# Schematics.net
KiCad netlist of a schematic drawn in Altium Designer
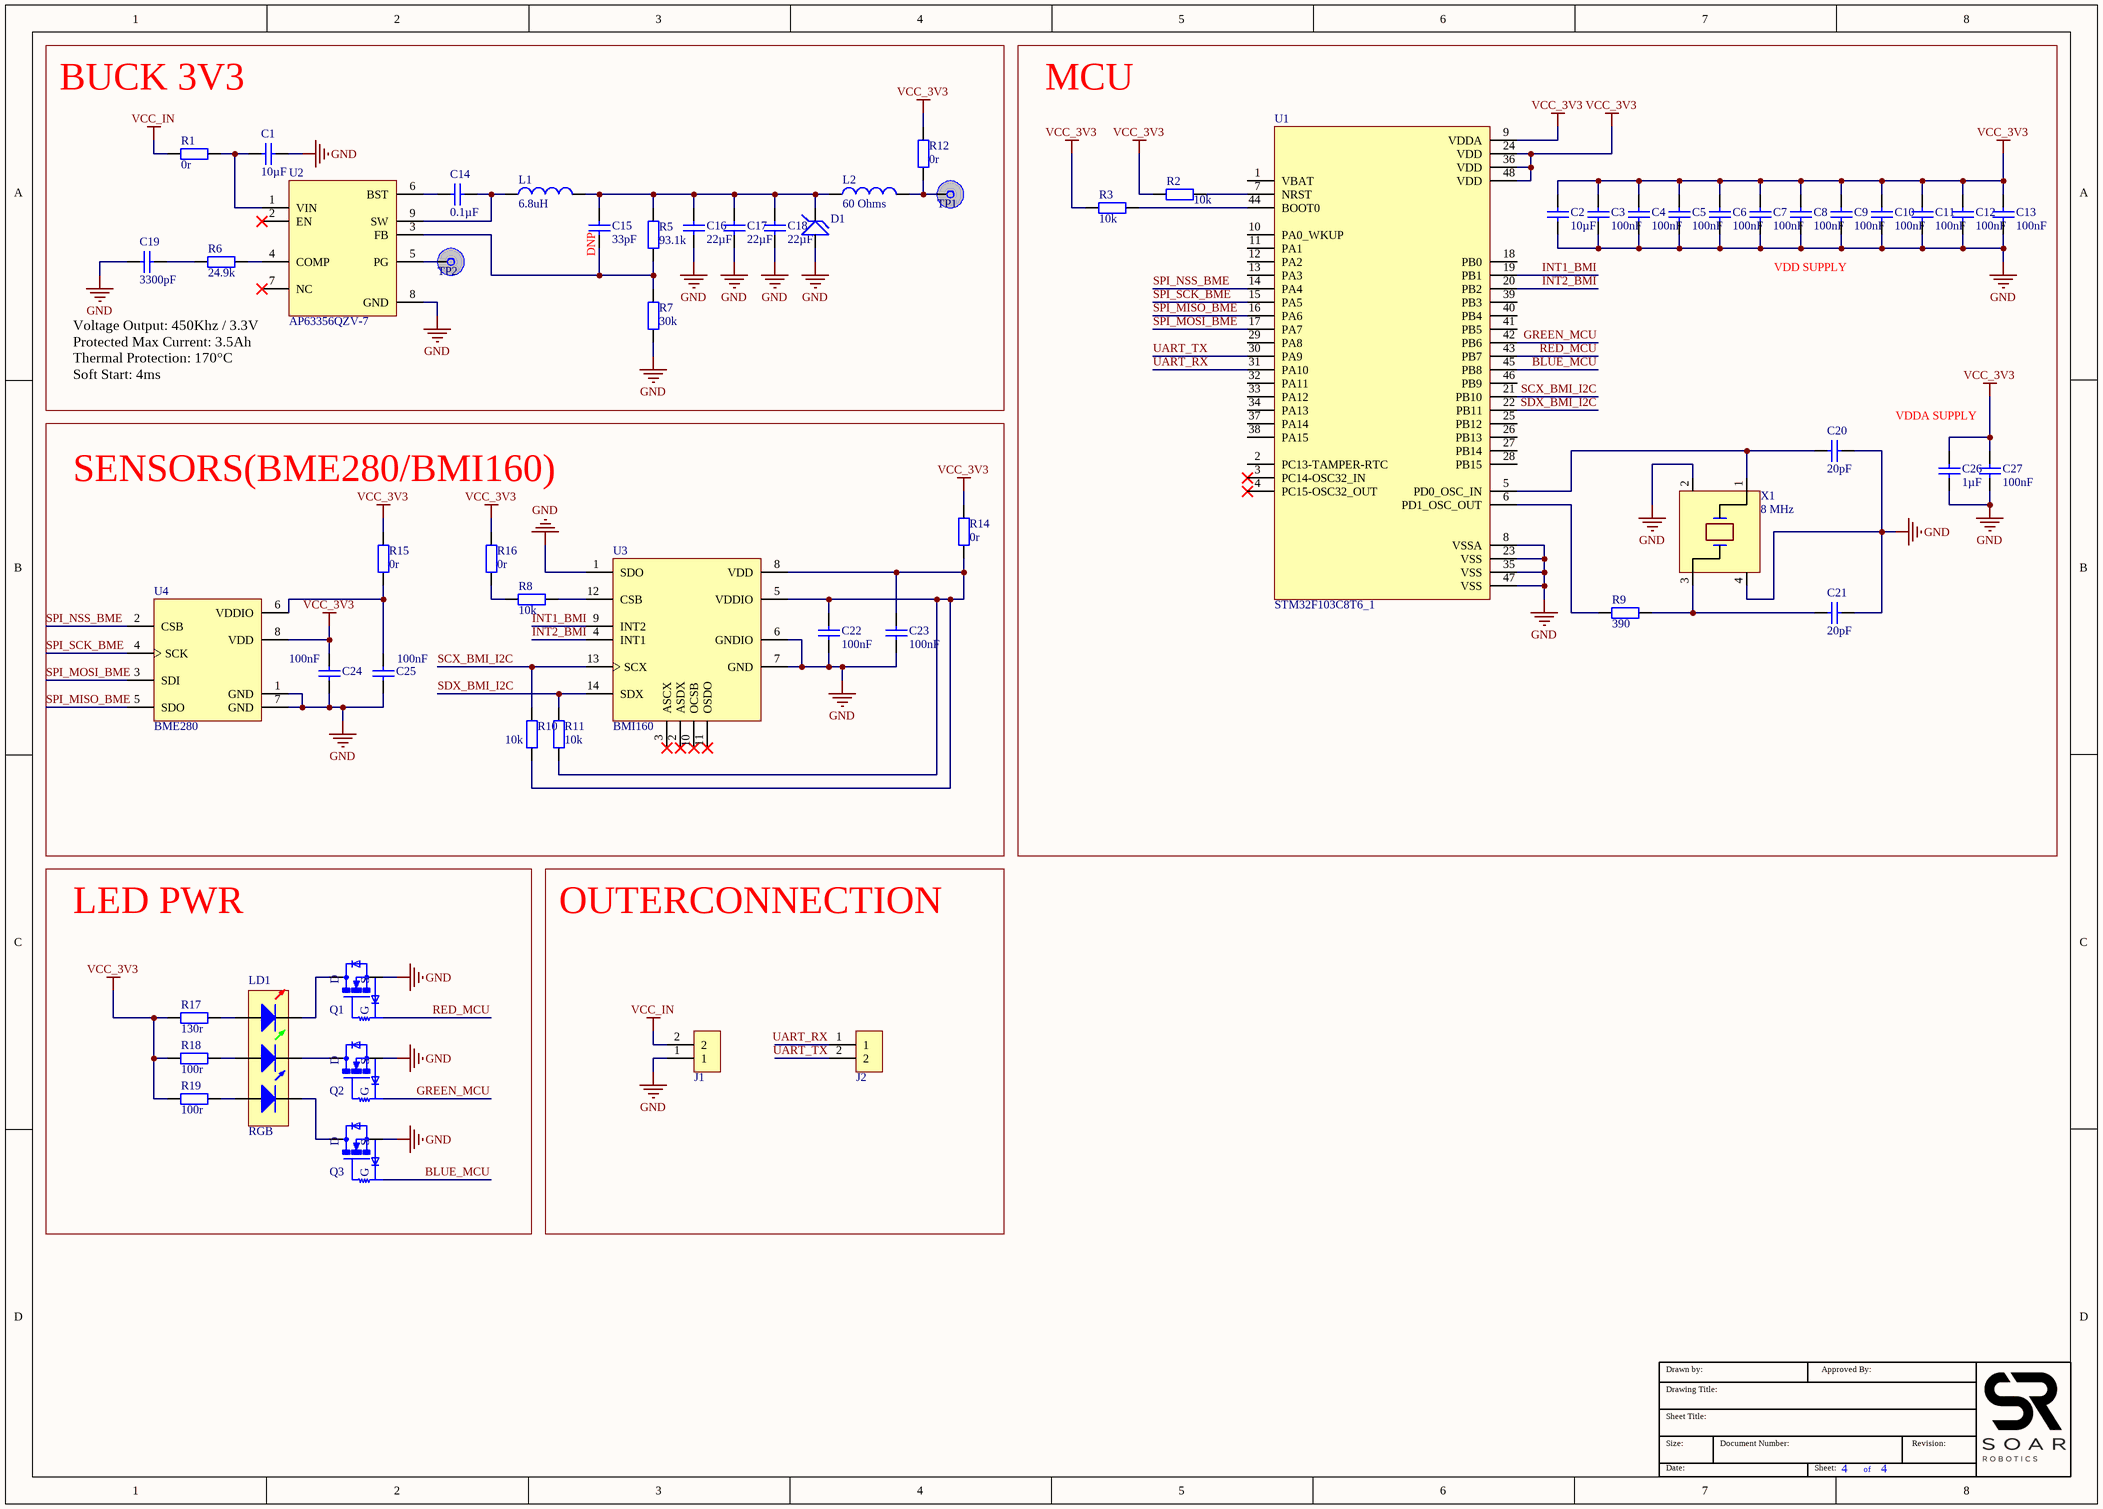
[diagram p0: Schematics.SchDoc]

(export (version "E")
  (design (tool "Eeschema 10.0.6"))
  (components
    (comp (ref "C1")
      (value "10µF")
      (footprint "CAP_0805")
      (description "10 µF ±10% 50V Ceramic Capacitor X5R 0805 (2012 Metric)")
      (fields (field (name "MANUFACTURER PART NUMBER") "GRM21BR61H106KE43L") (field (name "VOLTAGE") "50V"))
      (libsource (lib "MyCapLib") (part "GRM21BR61H106KE43L"))
    )
    (comp (ref "C2")
      (value "10µF")
      (footprint "CAP_0402")
      (description "10µF ±20% 6.3V Ceramic Capacitor X5R 0402 (1005 Metric)")
      (fields (field (name "MANUFACTURER PART NUMBER") "GRJ155R60J106ME11D") (field (name "VOLTAGE") "6.3V"))
      (libsource (lib "MyCapLib") (part "GRJ155R60J106ME11D"))
    )
    (comp (ref "C3")
      (value "100nF")
      (footprint "CAP_0603")
      (fields (field (name "Comment") "CAP"))
      (libsource (lib "MyCapLib") (part "CAP"))
    )
    (comp (ref "C4")
      (value "100nF")
      (footprint "CAP_0603")
      (fields (field (name "Comment") "CAP"))
      (libsource (lib "MyCapLib") (part "CAP"))
    )
    (comp (ref "C5")
      (value "100nF")
      (footprint "CAP_0603")
      (fields (field (name "Comment") "CAP"))
      (libsource (lib "MyCapLib") (part "CAP"))
    )
    (comp (ref "C6")
      (value "100nF")
      (footprint "CAP_0603")
      (fields (field (name "Comment") "CAP"))
      (libsource (lib "MyCapLib") (part "CAP"))
    )
    (comp (ref "C7")
      (value "100nF")
      (footprint "CAP_0603")
      (fields (field (name "Comment") "CAP"))
      (libsource (lib "MyCapLib") (part "CAP"))
    )
    (comp (ref "C8")
      (value "100nF")
      (footprint "CAP_0603")
      (fields (field (name "Comment") "CAP"))
      (libsource (lib "MyCapLib") (part "CAP"))
    )
    (comp (ref "C9")
      (value "100nF")
      (footprint "CAP_0603")
      (fields (field (name "Comment") "CAP"))
      (libsource (lib "MyCapLib") (part "CAP"))
    )
    (comp (ref "C10")
      (value "100nF")
      (footprint "CAP_0603")
      (fields (field (name "Comment") "CAP"))
      (libsource (lib "MyCapLib") (part "CAP"))
    )
    (comp (ref "C11")
      (value "100nF")
      (footprint "CAP_0603")
      (fields (field (name "Comment") "CAP"))
      (libsource (lib "MyCapLib") (part "CAP"))
    )
    (comp (ref "C12")
      (value "100nF")
      (footprint "CAP_0603")
      (fields (field (name "Comment") "CAP"))
      (libsource (lib "MyCapLib") (part "CAP"))
    )
    (comp (ref "C13")
      (value "100nF")
      (footprint "CAP_0603")
      (fields (field (name "Comment") "CAP"))
      (libsource (lib "MyCapLib") (part "CAP"))
    )
    (comp (ref "C14")
      (value "0.1µF")
      (footprint "CAP_0402")
      (description "0.1 µF ±10% 50V Ceramic Capacitor X7R 0402 (1005 Metric)")
      (fields (field (name "MANUFACTURER PART NUMBER") "04025C104KAT2A") (field (name "VOLTAGE") "50V"))
      (libsource (lib "MyCapLib") (part "04025C104KAT2A"))
    )
    (comp (ref "C15")
      (value "33pF")
      (footprint "CAP_0402")
      (description "33pF ±5% 50V Ceramic Capacitor C0G, NP0 0402 (1005 Metric)")
      (fields (field (name "MANUFACTURER PART NUMBER") "CL05C330JB5NNNC") (field (name "VOLTAGE") "50V"))
      (libsource (lib "MyCapLib") (part "CL05C330JB5NNNC"))
    )
    (comp (ref "C16")
      (value "22µF")
      (footprint "CAP_0603")
      (description "22 µF ±20% 6.3V Ceramic Capacitor X5R 0603 (1608 Metric)")
      (fields (field (name "MANUFACTURER PART NUMBER") "GRM188R60J226MEA0D") (field (name "VOLTAGE") "6.3V"))
      (libsource (lib "MyCapLib") (part "GRM188R60J226MEA0D"))
    )
    (comp (ref "C17")
      (value "22µF")
      (footprint "CAP_0603")
      (description "22 µF ±20% 6.3V Ceramic Capacitor X5R 0603 (1608 Metric)")
      (fields (field (name "MANUFACTURER PART NUMBER") "GRM188R60J226MEA0D") (field (name "VOLTAGE") "6.3V"))
      (libsource (lib "MyCapLib") (part "GRM188R60J226MEA0D"))
    )
    (comp (ref "C18")
      (value "22µF")
      (footprint "CAP_0603")
      (description "22 µF ±20% 6.3V Ceramic Capacitor X5R 0603 (1608 Metric)")
      (fields (field (name "MANUFACTURER PART NUMBER") "GRM188R60J226MEA0D") (field (name "VOLTAGE") "6.3V"))
      (libsource (lib "MyCapLib") (part "GRM188R60J226MEA0D"))
    )
    (comp (ref "C19")
      (value "3300pF")
      (footprint "CAP_0402")
      (description "3300pF ±10% 50V Ceramic Capacitor X7R 0402 (1005 Metric)")
      (fields (field (name "MANUFACTURER PART NUMBER") "CL05B332KB5NNNC") (field (name "VOLTAGE") "50V"))
      (libsource (lib "MyCapLib") (part "CL05B332KB5NNNC"))
    )
    (comp (ref "C20")
      (value "20pF")
      (footprint "CAP_0402")
      (description "20pF ±2% 50V Ceramic Capacitor C0G, NP0 0402 (1005 Metric)")
      (fields (field (name "MANUFACTURER PART NUMBER") "CC0402GRNPO9BN200") (field (name "VOLTAGE") "50v"))
      (libsource (lib "MyCapLib") (part "CC0402GRNPO9BN200"))
    )
    (comp (ref "C21")
      (value "20pF")
      (footprint "CAP_0402")
      (description "20pF ±2% 50V Ceramic Capacitor C0G, NP0 0402 (1005 Metric)")
      (fields (field (name "MANUFACTURER PART NUMBER") "CC0402GRNPO9BN200") (field (name "VOLTAGE") "50v"))
      (libsource (lib "MyCapLib") (part "CC0402GRNPO9BN200"))
    )
    (comp (ref "C22")
      (value "100nF")
      (footprint "CAP_0603")
      (fields (field (name "Comment") "CAP"))
      (libsource (lib "MyCapLib") (part "CAP"))
    )
    (comp (ref "C23")
      (value "100nF")
      (footprint "CAP_0603")
      (fields (field (name "Comment") "CAP"))
      (libsource (lib "MyCapLib") (part "CAP"))
    )
    (comp (ref "C24")
      (value "100nF")
      (footprint "CAP_0603")
      (fields (field (name "Comment") "CAP"))
      (libsource (lib "MyCapLib") (part "CAP"))
    )
    (comp (ref "C25")
      (value "100nF")
      (footprint "CAP_0603")
      (fields (field (name "Comment") "CAP"))
      (libsource (lib "MyCapLib") (part "CAP"))
    )
    (comp (ref "C26")
      (value "1µF")
      (footprint "CAP_0805")
      (description "1µF ±10% 25V Ceramic Capacitor X7R 0805 (2012 Metric)")
      (fields (field (name "MANUFACTURER PART NUMBER") "CL21B105KAFNFNE") (field (name "VOLTAGE") "25V"))
      (libsource (lib "MyCapLib") (part "CL21B105KAFNFNE"))
    )
    (comp (ref "C27")
      (value "100nF")
      (footprint "CAP_0603")
      (fields (field (name "Comment") "CAP"))
      (libsource (lib "MyCapLib") (part "CAP"))
    )
    (comp (ref "D1")
      (value "D6V3H1U2LP16-7")
      (footprint "U-DFN1610-2")
      (description "TVS DIODE 6.3V 11.5V U-DFN1610-2")
      (libsource (lib "MyDiodeLib") (part "D6V3H1U2LP16-7"))
    )
    (comp (ref "J1")
      (value "PRPC001DAAN-RC")
      (footprint "Header x2 Through Hole")
      (description "Connector Header Through Hole 2 position  2.54mm")
      (libsource (lib "MyConLib") (part "PRPC001DAAN-RC"))
    )
    (comp (ref "J2")
      (value "M50-3630242")
      (footprint "1.27MM 2X1 HEADER")
      (description "Connector Header Surface Mount 2 position 0.050\" (1.27mm)")
      (libsource (lib "MyConLib") (part "M50-3630242"))
    )
    (comp (ref "L1")
      (value "6.8uH")
      (footprint "74439346068")
      (description "6.8 µH Shielded Drum Core, Wirewound Inductor 6.5 A 17.6mOhm Nonstandard")
      (fields (field (name "MANUFACTURER PART NUMBER") "74439346068"))
      (libsource (lib "MyIndLib") (part "74439346068"))
    )
    (comp (ref "L2")
      (value "60 Ohms")
      (footprint "IND_0805")
      (description "60 Ohms @ 100MHz 1 Power Line Ferrite Bead 0805 (2012 Metric) 3.5A 20mOhm")
      (fields (field (name "MANUFACTURER PART NUMBER") "BLM21PG600SH1D"))
      (libsource (lib "MyIndLib") (part "BLM21PG600SH1D"))
    )
    (comp (ref "LD1")
      (value "EAST1616RGBB8")
      (footprint "SMD-RGB(1.60x1.60)")
      (fields (field (name "VOLTAGE") "2.05V Red, 2.2V Green, 2.2V Blue") (field (name "COLOR") "RGB"))
      (libsource (lib "MyLedLib") (part "EAST1616RGBB8"))
    )
    (comp (ref "Q1")
      (value "CSD13381F4")
      (footprint "3-XFDFN")
      (description "N-Channel 12 V 2.1A (Ta) 500mW (Ta) Surface Mount 3-PICOSTAR")
      (libsource (lib "MyMosfetLib") (part "CSD13381F4"))
    )
    (comp (ref "Q2")
      (value "CSD13381F4")
      (footprint "3-XFDFN")
      (description "N-Channel 12 V 2.1A (Ta) 500mW (Ta) Surface Mount 3-PICOSTAR")
      (libsource (lib "MyMosfetLib") (part "CSD13381F4"))
    )
    (comp (ref "Q3")
      (value "CSD13381F4")
      (footprint "3-XFDFN")
      (description "N-Channel 12 V 2.1A (Ta) 500mW (Ta) Surface Mount 3-PICOSTAR")
      (libsource (lib "MyMosfetLib") (part "CSD13381F4"))
    )
    (comp (ref "R1")
      (value "0r")
      (footprint "RES_0402")
      (description "RES SMD 0 OHM JUMPER 1/16W 0402")
      (fields (field (name "MANUFACTURER PART NUMBER") "RC0402JR-070RL") (field (name "POWER") "1/16w"))
      (libsource (lib "") (part "RC0402JR-070RL_1"))
    )
    (comp (ref "R2")
      (value "10k")
      (footprint "RES_0402")
      (description "RES 10K OHM 1% 1/16W 0402")
      (fields (field (name "TOLERANCE") "%1") (field (name "POWER") "1/16w"))
      (libsource (lib "") (part "RMCF0402FT10K0_2"))
    )
    (comp (ref "R3")
      (value "10k")
      (footprint "RES_0402")
      (description "RES 10K OHM 1% 1/16W 0402")
      (fields (field (name "TOLERANCE") "%1") (field (name "POWER") "1/16w"))
      (libsource (lib "MyResLib") (part "RMCF0402FT10K0"))
    )
    (comp (ref "R5")
      (value "93.1k")
      (footprint "RES_0402")
      (description "93.1 kOhms ±1% 0.063W, 1/16W Chip Resistor 0402 (1005 Metric) Moisture Resistant Thick Film")
      (fields (field (name "MANUFACTURER PART NUMBER") "RC0402FR-0793K1L") (field (name "POWER") "1/16w"))
      (libsource (lib "MyResLib") (part "RC0402FR-0793K1L"))
    )
    (comp (ref "R6")
      (value "24.9k")
      (footprint "RES_0402")
      (description "RES 24.9K OHM 1% 1/16W 0402")
      (fields (field (name "MANUFACTURER PART NUMBER") "RMCF0402FT24K9") (field (name "POWER") "1/16W"))
      (libsource (lib "MyResLib") (part "RMCF0402FT24K9"))
    )
    (comp (ref "R7")
      (value "30k")
      (footprint "RES_0402")
      (description "RES SMD 30K OHM 1% 1/16W 0402")
      (fields (field (name "MANUFACTURER PART NUMBER") "RC0402FR-0730KL") (field (name "POWER") "1/16w"))
      (libsource (lib "MyResLib") (part "RC0402FR-0730KL"))
    )
    (comp (ref "R8")
      (value "10k")
      (footprint "RES_0402")
      (description "RES 10K OHM 1% 1/16W 0402")
      (fields (field (name "TOLERANCE") "%1") (field (name "POWER") "1/16w"))
      (libsource (lib "MyResLib") (part "RMCF0402FT10K0"))
    )
    (comp (ref "R9")
      (value "390")
      (footprint "RES_0402")
      (description "390 Ohms ±1% 0.063W, 1/16W Chip Resistor 0402 (1005 Metric) Moisture Resistant Thick Film")
      (fields (field (name "MANUFACTURER PART NUMBER") "RC0402FR-07390RL") (field (name "POWER") "1/16W"))
      (libsource (lib "MyResLib") (part "RC0402FR-07390RL"))
    )
    (comp (ref "R10")
      (value "10k")
      (footprint "RES_0402")
      (description "RES 10K OHM 1% 1/16W 0402")
      (fields (field (name "TOLERANCE") "%1") (field (name "POWER") "1/16w"))
      (libsource (lib "") (part "RMCF0402FT10K0_1"))
    )
    (comp (ref "R11")
      (value "10k")
      (footprint "RES_0402")
      (description "RES 10K OHM 1% 1/16W 0402")
      (fields (field (name "TOLERANCE") "%1") (field (name "POWER") "1/16w"))
      (libsource (lib "") (part "RMCF0402FT10K0_1"))
    )
    (comp (ref "R12")
      (value "0r")
      (footprint "RES_0402")
      (description "RES SMD 0 OHM JUMPER 1/16W 0402")
      (fields (field (name "MANUFACTURER PART NUMBER") "RC0402JR-070RL") (field (name "POWER") "1/16w"))
      (libsource (lib "MyResLib") (part "RC0402JR-070RL"))
    )
    (comp (ref "R14")
      (value "0r")
      (footprint "RES_0402")
      (description "RES SMD 0 OHM JUMPER 1/16W 0402")
      (fields (field (name "MANUFACTURER PART NUMBER") "RC0402JR-070RL") (field (name "POWER") "1/16w"))
      (libsource (lib "MyResLib") (part "RC0402JR-070RL"))
    )
    (comp (ref "R15")
      (value "0r")
      (footprint "RES_0402")
      (description "RES SMD 0 OHM JUMPER 1/16W 0402")
      (fields (field (name "MANUFACTURER PART NUMBER") "RC0402JR-070RL") (field (name "POWER") "1/16w"))
      (libsource (lib "MyResLib") (part "RC0402JR-070RL"))
    )
    (comp (ref "R16")
      (value "0r")
      (footprint "RES_0402")
      (description "RES SMD 0 OHM JUMPER 1/16W 0402")
      (fields (field (name "MANUFACTURER PART NUMBER") "RC0402JR-070RL") (field (name "POWER") "1/16w"))
      (libsource (lib "MyResLib") (part "RC0402JR-070RL"))
    )
    (comp (ref "R17")
      (value "130r")
      (footprint "RES_0402")
      (description "RES SMD 130 OHM 5% 1/16W 0402")
      (fields (field (name "MANUFACTURER PART NUMBER") "RC0402JR-07130RL") (field (name "POWER") "1/16w"))
      (libsource (lib "MyResLib") (part "RC0402JR-07130RL"))
    )
    (comp (ref "R18")
      (value "100r")
      (footprint "RES_0402")
      (description "RES SMD 100 OHM 1% 1/16W 0402")
      (fields (field (name "MANUFACTURER PART NUMBER") "RC0402FR-07100RL") (field (name "POWER") "1/16w"))
      (libsource (lib "MyResLib") (part "RC0402FR-07100RL"))
    )
    (comp (ref "R19")
      (value "100r")
      (footprint "RES_0402")
      (description "RES SMD 100 OHM 1% 1/16W 0402")
      (fields (field (name "MANUFACTURER PART NUMBER") "RC0402FR-07100RL") (field (name "POWER") "1/16w"))
      (libsource (lib "MyResLib") (part "RC0402FR-07100RL"))
    )
    (comp (ref "TP1")
      (value "TP")
      (footprint "TP")
      (description "Test Point")
      (libsource (lib "MyConLib") (part "TP"))
    )
    (comp (ref "TP2")
      (value "TP")
      (footprint "TP")
      (description "Test Point")
      (libsource (lib "MyConLib") (part "TP"))
    )
    (comp (ref "U1")
      (value "STM32F103C8T6_1")
      (footprint "QFP50P900X900X160-48N")
      (fields (field (name "MANUFACTURER PART NUMBER") "STM32F103C8T6"))
      (libsource (lib "MyICLib") (part "STM32F103C8T6_1"))
    )
    (comp (ref "U2")
      (value "AP63356QZV-7")
      (footprint "V-DFN3020-13")
      (description "Buck Switching Regulator IC Positive Adjustable 0.8V 1 Output 3.5A 13-PowerVFDFN")
      (libsource (lib "MyICLib") (part "AP63356QZV-7"))
    )
    (comp (ref "U3")
      (value "BMI160")
      (footprint "PQFN50P250X300X88-14N")
      (description "Accelerometer, Gyroscope, 6 Axis Sensor IÂ²C, SPI Output")
      (libsource (lib "MyICLib") (part "BMI160"))
    )
    (comp (ref "U4")
      (value "BME280")
      (footprint "PSON65P250X250X100-8N")
      (libsource (lib "MyICLib") (part "BME280"))
    )
    (comp (ref "X1")
      (value "8 MHz")
      (footprint "XTAL_ECS-240-8-33-AGN-TR")
      (description "8 MHz ±20ppm Crystal 12pF 400 Ohms 4-SMD, No Lead")
      (fields (field (name "Comment") "ECS-80-12-33-JGN-TR"))
      (libsource (lib "MyXtalLib") (part "ECS-80-12-33-JGN-TR"))
    )
  )
  (nets
    (net (code "2") (name "/BLUE_MCU") (class "Default")
      (node (ref "Q3") (pin "1") (pinfunction "G_1") (pintype "passive"))
      (node (ref "U1") (pin "45") (pinfunction "PB8_45") (pintype "passive"))
    )
    (net (code "3") (name "/GREEN_MCU") (class "Default")
      (node (ref "Q2") (pin "1") (pinfunction "G_1") (pintype "passive"))
      (node (ref "U1") (pin "42") (pinfunction "PB6_42") (pintype "passive"))
    )
    (net (code "4") (name "/INT1_BMI") (class "Default")
      (node (ref "U1") (pin "19") (pinfunction "PB1_19") (pintype "passive"))
      (node (ref "U3") (pin "9") (pinfunction "INT2_9") (pintype "passive"))
    )
    (net (code "5") (name "/INT2_BMI") (class "Default")
      (node (ref "U1") (pin "20") (pinfunction "PB2_20") (pintype "passive"))
      (node (ref "U3") (pin "4") (pinfunction "INT1_4") (pintype "passive"))
    )
    (net (code "6") (name "/RED_MCU") (class "Default")
      (node (ref "Q1") (pin "1") (pinfunction "G_1") (pintype "passive"))
      (node (ref "U1") (pin "43") (pinfunction "PB7_43") (pintype "passive"))
    )
    (net (code "7") (name "/SCX_BMI_I2C") (class "Default")
      (node (ref "R10") (pin "2") (pinfunction "2_2") (pintype "passive"))
      (node (ref "U1") (pin "21") (pinfunction "PB10_21") (pintype "passive"))
      (node (ref "U3") (pin "13") (pinfunction "SCX_13") (pintype "passive"))
    )
    (net (code "8") (name "/SDX_BMI_I2C") (class "Default")
      (node (ref "R11") (pin "2") (pinfunction "2_2") (pintype "passive"))
      (node (ref "U1") (pin "22") (pinfunction "PB11_22") (pintype "passive"))
      (node (ref "U3") (pin "14") (pinfunction "SDX_14") (pintype "passive"))
    )
    (net (code "9") (name "/SPI_MISO_BME") (class "Default")
      (node (ref "U1") (pin "16") (pinfunction "PA6_16") (pintype "passive"))
      (node (ref "U4") (pin "5") (pinfunction "SDO_5") (pintype "passive"))
    )
    (net (code "10") (name "/SPI_MOSI_BME") (class "Default")
      (node (ref "U1") (pin "17") (pinfunction "PA7_17") (pintype "passive"))
      (node (ref "U4") (pin "3") (pinfunction "SDI_3") (pintype "passive"))
    )
    (net (code "11") (name "/SPI_NSS_BME") (class "Default")
      (node (ref "U1") (pin "14") (pinfunction "PA4_14") (pintype "passive"))
      (node (ref "U4") (pin "2") (pinfunction "CSB_2") (pintype "passive"))
    )
    (net (code "12") (name "/SPI_SCK_BME") (class "Default")
      (node (ref "U1") (pin "15") (pinfunction "PA5_15") (pintype "passive"))
      (node (ref "U4") (pin "4") (pinfunction "SCK_4") (pintype "passive"))
    )
    (net (code "13") (name "/UART_RX") (class "Default")
      (node (ref "J2") (pin "1") (pinfunction "1_1") (pintype "passive"))
      (node (ref "U1") (pin "31") (pinfunction "PA10_31") (pintype "passive"))
    )
    (net (code "14") (name "/UART_TX") (class "Default")
      (node (ref "J2") (pin "2") (pinfunction "2_2") (pintype "passive"))
      (node (ref "U1") (pin "30") (pinfunction "PA9_30") (pintype "passive"))
    )
    (net (code "15") (name "GND") (class "Default")
      (node (ref "C1") (pin "1") (pinfunction "1_1") (pintype "passive"))
      (node (ref "C10") (pin "2") (pinfunction "2_2") (pintype "passive"))
      (node (ref "C11") (pin "2") (pinfunction "2_2") (pintype "passive"))
      (node (ref "C12") (pin "2") (pinfunction "2_2") (pintype "passive"))
      (node (ref "C13") (pin "2") (pinfunction "2_2") (pintype "passive"))
      (node (ref "C16") (pin "1") (pinfunction "1_1") (pintype "passive"))
      (node (ref "C17") (pin "1") (pinfunction "1_1") (pintype "passive"))
      (node (ref "C18") (pin "1") (pinfunction "1_1") (pintype "passive"))
      (node (ref "C19") (pin "1") (pinfunction "1_1") (pintype "passive"))
      (node (ref "C2") (pin "1") (pinfunction "1_1") (pintype "passive"))
      (node (ref "C20") (pin "2") (pinfunction "2_2") (pintype "passive"))
      (node (ref "C21") (pin "2") (pinfunction "2_2") (pintype "passive"))
      (node (ref "C22") (pin "2") (pinfunction "2_2") (pintype "passive"))
      (node (ref "C23") (pin "2") (pinfunction "2_2") (pintype "passive"))
      (node (ref "C24") (pin "1") (pinfunction "1_1") (pintype "passive"))
      (node (ref "C25") (pin "1") (pinfunction "1_1") (pintype "passive"))
      (node (ref "C26") (pin "1") (pinfunction "1_1") (pintype "passive"))
      (node (ref "C27") (pin "2") (pinfunction "2_2") (pintype "passive"))
      (node (ref "C3") (pin "2") (pinfunction "2_2") (pintype "passive"))
      (node (ref "C4") (pin "2") (pinfunction "2_2") (pintype "passive"))
      (node (ref "C5") (pin "2") (pinfunction "2_2") (pintype "passive"))
      (node (ref "C6") (pin "2") (pinfunction "2_2") (pintype "passive"))
      (node (ref "C7") (pin "2") (pinfunction "2_2") (pintype "passive"))
      (node (ref "C8") (pin "2") (pinfunction "2_2") (pintype "passive"))
      (node (ref "C9") (pin "2") (pinfunction "2_2") (pintype "passive"))
      (node (ref "D1") (pin "1") (pinfunction "1_1") (pintype "passive"))
      (node (ref "J1") (pin "1") (pinfunction "1_1") (pintype "passive"))
      (node (ref "Q1") (pin "2") (pinfunction "S_2") (pintype "passive"))
      (node (ref "Q2") (pin "2") (pinfunction "S_2") (pintype "passive"))
      (node (ref "Q3") (pin "2") (pinfunction "S_2") (pintype "passive"))
      (node (ref "R7") (pin "1") (pinfunction "1_1") (pintype "passive"))
      (node (ref "U1") (pin "23") (pinfunction "VSS_23") (pintype "passive"))
      (node (ref "U1") (pin "35") (pinfunction "VSS_35") (pintype "passive"))
      (node (ref "U1") (pin "47") (pinfunction "VSS_47") (pintype "passive"))
      (node (ref "U1") (pin "8") (pinfunction "VSSA_8") (pintype "passive"))
      (node (ref "U2") (pin "8") (pinfunction "GND_8") (pintype "power_in"))
      (node (ref "U3") (pin "1") (pinfunction "SDO_1") (pintype "passive"))
      (node (ref "U3") (pin "6") (pinfunction "GNDIO_6") (pintype "passive"))
      (node (ref "U3") (pin "7") (pinfunction "GND_7") (pintype "passive"))
      (node (ref "U4") (pin "1") (pinfunction "GND_1") (pintype "passive"))
      (node (ref "U4") (pin "7") (pinfunction "GND_7") (pintype "passive"))
      (node (ref "X1") (pin "2") (pinfunction "2_2") (pintype "passive"))
      (node (ref "X1") (pin "4") (pinfunction "4_4") (pintype "passive"))
    )
    (net (code "16") (name "Net-(C15-Pad2)") (class "Default")
      (node (ref "C15") (pin "2") (pinfunction "2_2") (pintype "passive"))
      (node (ref "C16") (pin "2") (pinfunction "2_2") (pintype "passive"))
      (node (ref "C17") (pin "2") (pinfunction "2_2") (pintype "passive"))
      (node (ref "C18") (pin "2") (pinfunction "2_2") (pintype "passive"))
      (node (ref "D1") (pin "2") (pinfunction "2_2") (pintype "passive"))
      (node (ref "L1") (pin "2") (pinfunction "2_2") (pintype "passive"))
      (node (ref "L2") (pin "1") (pinfunction "1_1") (pintype "passive"))
      (node (ref "R5") (pin "2") (pinfunction "2_2") (pintype "passive"))
    )
    (net (code "17") (name "Net-(C19-Pad2)") (class "Default")
      (node (ref "C19") (pin "2") (pinfunction "2_2") (pintype "passive"))
      (node (ref "R6") (pin "1") (pinfunction "1_1") (pintype "passive"))
    )
    (net (code "18") (name "Net-(C21-Pad1)") (class "Default")
      (node (ref "C21") (pin "1") (pinfunction "1_1") (pintype "passive"))
      (node (ref "R9") (pin "2") (pinfunction "2_2") (pintype "passive"))
      (node (ref "X1") (pin "3") (pinfunction "3_3") (pintype "passive"))
    )
    (net (code "19") (name "Net-(L2-Pad2)") (class "Default")
      (node (ref "L2") (pin "2") (pinfunction "2_2") (pintype "passive"))
      (node (ref "R12") (pin "1") (pinfunction "1_1") (pintype "passive"))
      (node (ref "TP1") (pin "1") (pinfunction "1_1") (pintype "passive"))
    )
    (net (code "20") (name "Net-(LD1-BA)") (class "Default")
      (node (ref "LD1") (pin "6") (pinfunction "BA_6") (pintype "passive"))
      (node (ref "R19") (pin "2") (pinfunction "2_2") (pintype "passive"))
    )
    (net (code "21") (name "Net-(LD1-BC)") (class "Default")
      (node (ref "LD1") (pin "5") (pinfunction "BC_5") (pintype "passive"))
      (node (ref "Q3") (pin "3") (pinfunction "D_3") (pintype "passive"))
    )
    (net (code "22") (name "Net-(LD1-GA)") (class "Default")
      (node (ref "LD1") (pin "2") (pinfunction "GA_2") (pintype "passive"))
      (node (ref "R18") (pin "2") (pinfunction "2_2") (pintype "passive"))
    )
    (net (code "23") (name "Net-(LD1-GC)") (class "Default")
      (node (ref "LD1") (pin "1") (pinfunction "GC_1") (pintype "passive"))
      (node (ref "Q2") (pin "3") (pinfunction "D_3") (pintype "passive"))
    )
    (net (code "24") (name "Net-(LD1-RA)") (class "Default")
      (node (ref "LD1") (pin "4") (pinfunction "RA_4") (pintype "passive"))
      (node (ref "R17") (pin "2") (pinfunction "2_2") (pintype "passive"))
    )
    (net (code "25") (name "Net-(LD1-RC)") (class "Default")
      (node (ref "LD1") (pin "3") (pinfunction "RC_3") (pintype "passive"))
      (node (ref "Q1") (pin "3") (pinfunction "D_3") (pintype "passive"))
    )
    (net (code "26") (name "Net-(R16-Pad1)") (class "Default")
      (node (ref "R16") (pin "1") (pinfunction "1_1") (pintype "passive"))
      (node (ref "R8") (pin "2") (pinfunction "2_2") (pintype "passive"))
    )
    (net (code "27") (name "Net-(U1-BOOT0)") (class "Default")
      (node (ref "R3") (pin "1") (pinfunction "1_1") (pintype "passive"))
      (node (ref "U1") (pin "44") (pinfunction "BOOT0_44") (pintype "passive"))
    )
    (net (code "28") (name "Net-(U1-NRST)") (class "Default")
      (node (ref "R2") (pin "2") (pinfunction "2_2") (pintype "passive"))
      (node (ref "U1") (pin "7") (pinfunction "NRST_7") (pintype "passive"))
    )
    (net (code "29") (name "Net-(U1-PD0_OSC_IN)") (class "Default")
      (node (ref "C20") (pin "1") (pinfunction "1_1") (pintype "passive"))
      (node (ref "U1") (pin "5") (pinfunction "PD0_OSC_IN_5") (pintype "passive"))
      (node (ref "X1") (pin "1") (pinfunction "1_1") (pintype "passive"))
    )
    (net (code "30") (name "Net-(U1-PD1_OSC_OUT)") (class "Default")
      (node (ref "R9") (pin "1") (pinfunction "1_1") (pintype "passive"))
      (node (ref "U1") (pin "6") (pinfunction "PD1_OSC_OUT_6") (pintype "passive"))
    )
    (net (code "31") (name "Net-(U2-BST)") (class "Default")
      (node (ref "C14") (pin "2") (pinfunction "2_2") (pintype "passive"))
      (node (ref "U2") (pin "6") (pinfunction "BST_6") (pintype "passive"))
    )
    (net (code "32") (name "Net-(U2-COMP)") (class "Default")
      (node (ref "R6") (pin "2") (pinfunction "2_2") (pintype "passive"))
      (node (ref "U2") (pin "4") (pinfunction "COMP_4") (pintype "passive"))
    )
    (net (code "33") (name "Net-(U2-FB)") (class "Default")
      (node (ref "C15") (pin "1") (pinfunction "1_1") (pintype "passive"))
      (node (ref "R5") (pin "1") (pinfunction "1_1") (pintype "passive"))
      (node (ref "R7") (pin "2") (pinfunction "2_2") (pintype "passive"))
      (node (ref "U2") (pin "3") (pinfunction "FB_3") (pintype "passive"))
    )
    (net (code "34") (name "Net-(U2-PG)") (class "Default")
      (node (ref "TP2") (pin "1") (pinfunction "1_1") (pintype "passive"))
      (node (ref "U2") (pin "5") (pinfunction "PG_5") (pintype "passive"))
    )
    (net (code "35") (name "Net-(U2-SW)") (class "Default")
      (node (ref "C14") (pin "1") (pinfunction "1_1") (pintype "passive"))
      (node (ref "L1") (pin "1") (pinfunction "1_1") (pintype "passive"))
      (node (ref "U2") (pin "9") (pinfunction "SW_9") (pintype "passive"))
    )
    (net (code "36") (name "Net-(U2-VIN)") (class "Default")
      (node (ref "C1") (pin "2") (pinfunction "2_2") (pintype "passive"))
      (node (ref "R1") (pin "2") (pinfunction "2_2") (pintype "passive"))
      (node (ref "U2") (pin "1") (pinfunction "VIN_1") (pintype "passive"))
    )
    (net (code "37") (name "Net-(U3-CSB)") (class "Default")
      (node (ref "R8") (pin "1") (pinfunction "1_1") (pintype "passive"))
      (node (ref "U3") (pin "12") (pinfunction "CSB_12") (pintype "passive"))
    )
    (net (code "38") (name "Net-(U3-VDD)") (class "Default")
      (node (ref "C22") (pin "1") (pinfunction "1_1") (pintype "passive"))
      (node (ref "C23") (pin "1") (pinfunction "1_1") (pintype "passive"))
      (node (ref "R10") (pin "1") (pinfunction "1_1") (pintype "passive"))
      (node (ref "R11") (pin "1") (pinfunction "1_1") (pintype "passive"))
      (node (ref "R14") (pin "1") (pinfunction "1_1") (pintype "passive"))
      (node (ref "U3") (pin "5") (pinfunction "VDDIO_5") (pintype "passive"))
      (node (ref "U3") (pin "8") (pinfunction "VDD_8") (pintype "passive"))
    )
    (net (code "39") (name "Net-(U4-VDDIO)") (class "Default")
      (node (ref "C25") (pin "2") (pinfunction "2_2") (pintype "passive"))
      (node (ref "R15") (pin "1") (pinfunction "1_1") (pintype "passive"))
      (node (ref "U4") (pin "6") (pinfunction "VDDIO_6") (pintype "passive"))
    )
    (net (code "40") (name "VCC_3V3") (class "Default")
      (node (ref "C10") (pin "1") (pinfunction "1_1") (pintype "passive"))
      (node (ref "C11") (pin "1") (pinfunction "1_1") (pintype "passive"))
      (node (ref "C12") (pin "1") (pinfunction "1_1") (pintype "passive"))
      (node (ref "C13") (pin "1") (pinfunction "1_1") (pintype "passive"))
      (node (ref "C2") (pin "2") (pinfunction "2_2") (pintype "passive"))
      (node (ref "C24") (pin "2") (pinfunction "2_2") (pintype "passive"))
      (node (ref "C26") (pin "2") (pinfunction "2_2") (pintype "passive"))
      (node (ref "C27") (pin "1") (pinfunction "1_1") (pintype "passive"))
      (node (ref "C3") (pin "1") (pinfunction "1_1") (pintype "passive"))
      (node (ref "C4") (pin "1") (pinfunction "1_1") (pintype "passive"))
      (node (ref "C5") (pin "1") (pinfunction "1_1") (pintype "passive"))
      (node (ref "C6") (pin "1") (pinfunction "1_1") (pintype "passive"))
      (node (ref "C7") (pin "1") (pinfunction "1_1") (pintype "passive"))
      (node (ref "C8") (pin "1") (pinfunction "1_1") (pintype "passive"))
      (node (ref "C9") (pin "1") (pinfunction "1_1") (pintype "passive"))
      (node (ref "R12") (pin "2") (pinfunction "2_2") (pintype "passive"))
      (node (ref "R14") (pin "2") (pinfunction "2_2") (pintype "passive"))
      (node (ref "R15") (pin "2") (pinfunction "2_2") (pintype "passive"))
      (node (ref "R16") (pin "2") (pinfunction "2_2") (pintype "passive"))
      (node (ref "R17") (pin "1") (pinfunction "1_1") (pintype "passive"))
      (node (ref "R18") (pin "1") (pinfunction "1_1") (pintype "passive"))
      (node (ref "R19") (pin "1") (pinfunction "1_1") (pintype "passive"))
      (node (ref "R2") (pin "1") (pinfunction "1_1") (pintype "passive"))
      (node (ref "R3") (pin "2") (pinfunction "2_2") (pintype "passive"))
      (node (ref "U1") (pin "24") (pinfunction "VDD_24") (pintype "passive"))
      (node (ref "U1") (pin "36") (pinfunction "VDD_36") (pintype "passive"))
      (node (ref "U1") (pin "48") (pinfunction "VDD_48") (pintype "passive"))
      (node (ref "U1") (pin "9") (pinfunction "VDDA_9") (pintype "passive"))
      (node (ref "U4") (pin "8") (pinfunction "VDD_8") (pintype "passive"))
    )
    (net (code "41") (name "VCC_IN") (class "Default")
      (node (ref "J1") (pin "2") (pinfunction "2_2") (pintype "passive"))
      (node (ref "R1") (pin "1") (pinfunction "1_1") (pintype "passive"))
    )
    (net (code "42") (name "unconnected-(U1-PA0_WKUP-Pad10)") (class "Default")
      (node (ref "U1") (pin "10") (pinfunction "PA0_WKUP_10") (pintype "passive"))
    )
    (net (code "43") (name "unconnected-(U1-PA1-Pad11)") (class "Default")
      (node (ref "U1") (pin "11") (pinfunction "PA1_11") (pintype "passive"))
    )
    (net (code "44") (name "unconnected-(U1-PA2-Pad12)") (class "Default")
      (node (ref "U1") (pin "12") (pinfunction "PA2_12") (pintype "passive"))
    )
    (net (code "45") (name "unconnected-(U1-PA3-Pad13)") (class "Default")
      (node (ref "U1") (pin "13") (pinfunction "PA3_13") (pintype "passive"))
    )
    (net (code "46") (name "unconnected-(U1-PA8-Pad29)") (class "Default")
      (node (ref "U1") (pin "29") (pinfunction "PA8_29") (pintype "passive"))
    )
    (net (code "47") (name "unconnected-(U1-PA11-Pad32)") (class "Default")
      (node (ref "U1") (pin "32") (pinfunction "PA11_32") (pintype "passive"))
    )
    (net (code "48") (name "unconnected-(U1-PA12-Pad33)") (class "Default")
      (node (ref "U1") (pin "33") (pinfunction "PA12_33") (pintype "passive"))
    )
    (net (code "49") (name "unconnected-(U1-PA13-Pad34)") (class "Default")
      (node (ref "U1") (pin "34") (pinfunction "PA13_34") (pintype "passive"))
    )
    (net (code "50") (name "unconnected-(U1-PA14-Pad37)") (class "Default")
      (node (ref "U1") (pin "37") (pinfunction "PA14_37") (pintype "passive"))
    )
    (net (code "51") (name "unconnected-(U1-PA15-Pad38)") (class "Default")
      (node (ref "U1") (pin "38") (pinfunction "PA15_38") (pintype "passive"))
    )
    (net (code "52") (name "unconnected-(U1-PB0-Pad18)") (class "Default")
      (node (ref "U1") (pin "18") (pinfunction "PB0_18") (pintype "passive"))
    )
    (net (code "53") (name "unconnected-(U1-PB3-Pad39)") (class "Default")
      (node (ref "U1") (pin "39") (pinfunction "PB3_39") (pintype "passive"))
    )
    (net (code "54") (name "unconnected-(U1-PB4-Pad40)") (class "Default")
      (node (ref "U1") (pin "40") (pinfunction "PB4_40") (pintype "passive"))
    )
    (net (code "55") (name "unconnected-(U1-PB5-Pad41)") (class "Default")
      (node (ref "U1") (pin "41") (pinfunction "PB5_41") (pintype "passive"))
    )
    (net (code "56") (name "unconnected-(U1-PB9-Pad46)") (class "Default")
      (node (ref "U1") (pin "46") (pinfunction "PB9_46") (pintype "passive"))
    )
    (net (code "57") (name "unconnected-(U1-PB12-Pad25)") (class "Default")
      (node (ref "U1") (pin "25") (pinfunction "PB12_25") (pintype "passive"))
    )
    (net (code "58") (name "unconnected-(U1-PB13-Pad26)") (class "Default")
      (node (ref "U1") (pin "26") (pinfunction "PB13_26") (pintype "passive"))
    )
    (net (code "59") (name "unconnected-(U1-PB14-Pad27)") (class "Default")
      (node (ref "U1") (pin "27") (pinfunction "PB14_27") (pintype "passive"))
    )
    (net (code "60") (name "unconnected-(U1-PB15-Pad28)") (class "Default")
      (node (ref "U1") (pin "28") (pinfunction "PB15_28") (pintype "passive"))
    )
    (net (code "61") (name "unconnected-(U1-PC13-TAMPER-RTC-Pad2)") (class "Default")
      (node (ref "U1") (pin "2") (pinfunction "PC13-TAMPER-RTC_2") (pintype "passive"))
    )
    (net (code "62") (name "unconnected-(U1-PC14-OSC32_IN-Pad3)") (class "Default")
      (node (ref "U1") (pin "3") (pinfunction "PC14-OSC32_IN_3") (pintype "passive+no_connect"))
    )
    (net (code "63") (name "unconnected-(U1-PC15-OSC32_OUT-Pad4)") (class "Default")
      (node (ref "U1") (pin "4") (pinfunction "PC15-OSC32_OUT_4") (pintype "passive+no_connect"))
    )
    (net (code "64") (name "unconnected-(U1-VBAT-Pad1)") (class "Default")
      (node (ref "U1") (pin "1") (pinfunction "VBAT_1") (pintype "passive"))
    )
    (net (code "65") (name "unconnected-(U2-EN-Pad2)") (class "Default")
      (node (ref "U2") (pin "2") (pinfunction "EN_2") (pintype "passive+no_connect"))
    )
    (net (code "66") (name "unconnected-(U2-NC-Pad7)") (class "Default")
      (node (ref "U2") (pin "7") (pinfunction "NC_7") (pintype "passive+no_connect"))
    )
    (net (code "67") (name "unconnected-(U3-ASCX-Pad3)") (class "Default")
      (node (ref "U3") (pin "3") (pinfunction "ASCX_3") (pintype "passive+no_connect"))
    )
    (net (code "68") (name "unconnected-(U3-ASDX-Pad2)") (class "Default")
      (node (ref "U3") (pin "2") (pinfunction "ASDX_2") (pintype "passive+no_connect"))
    )
    (net (code "69") (name "unconnected-(U3-OCSB-Pad10)") (class "Default")
      (node (ref "U3") (pin "10") (pinfunction "OCSB_10") (pintype "passive+no_connect"))
    )
    (net (code "70") (name "unconnected-(U3-OSDO-Pad11)") (class "Default")
      (node (ref "U3") (pin "11") (pinfunction "OSDO_11") (pintype "passive+no_connect"))
    )
  )
)
